# Sparkfun_TMP117_Qwiic.net
KiCad netlist of a schematic drawn in EAGLE
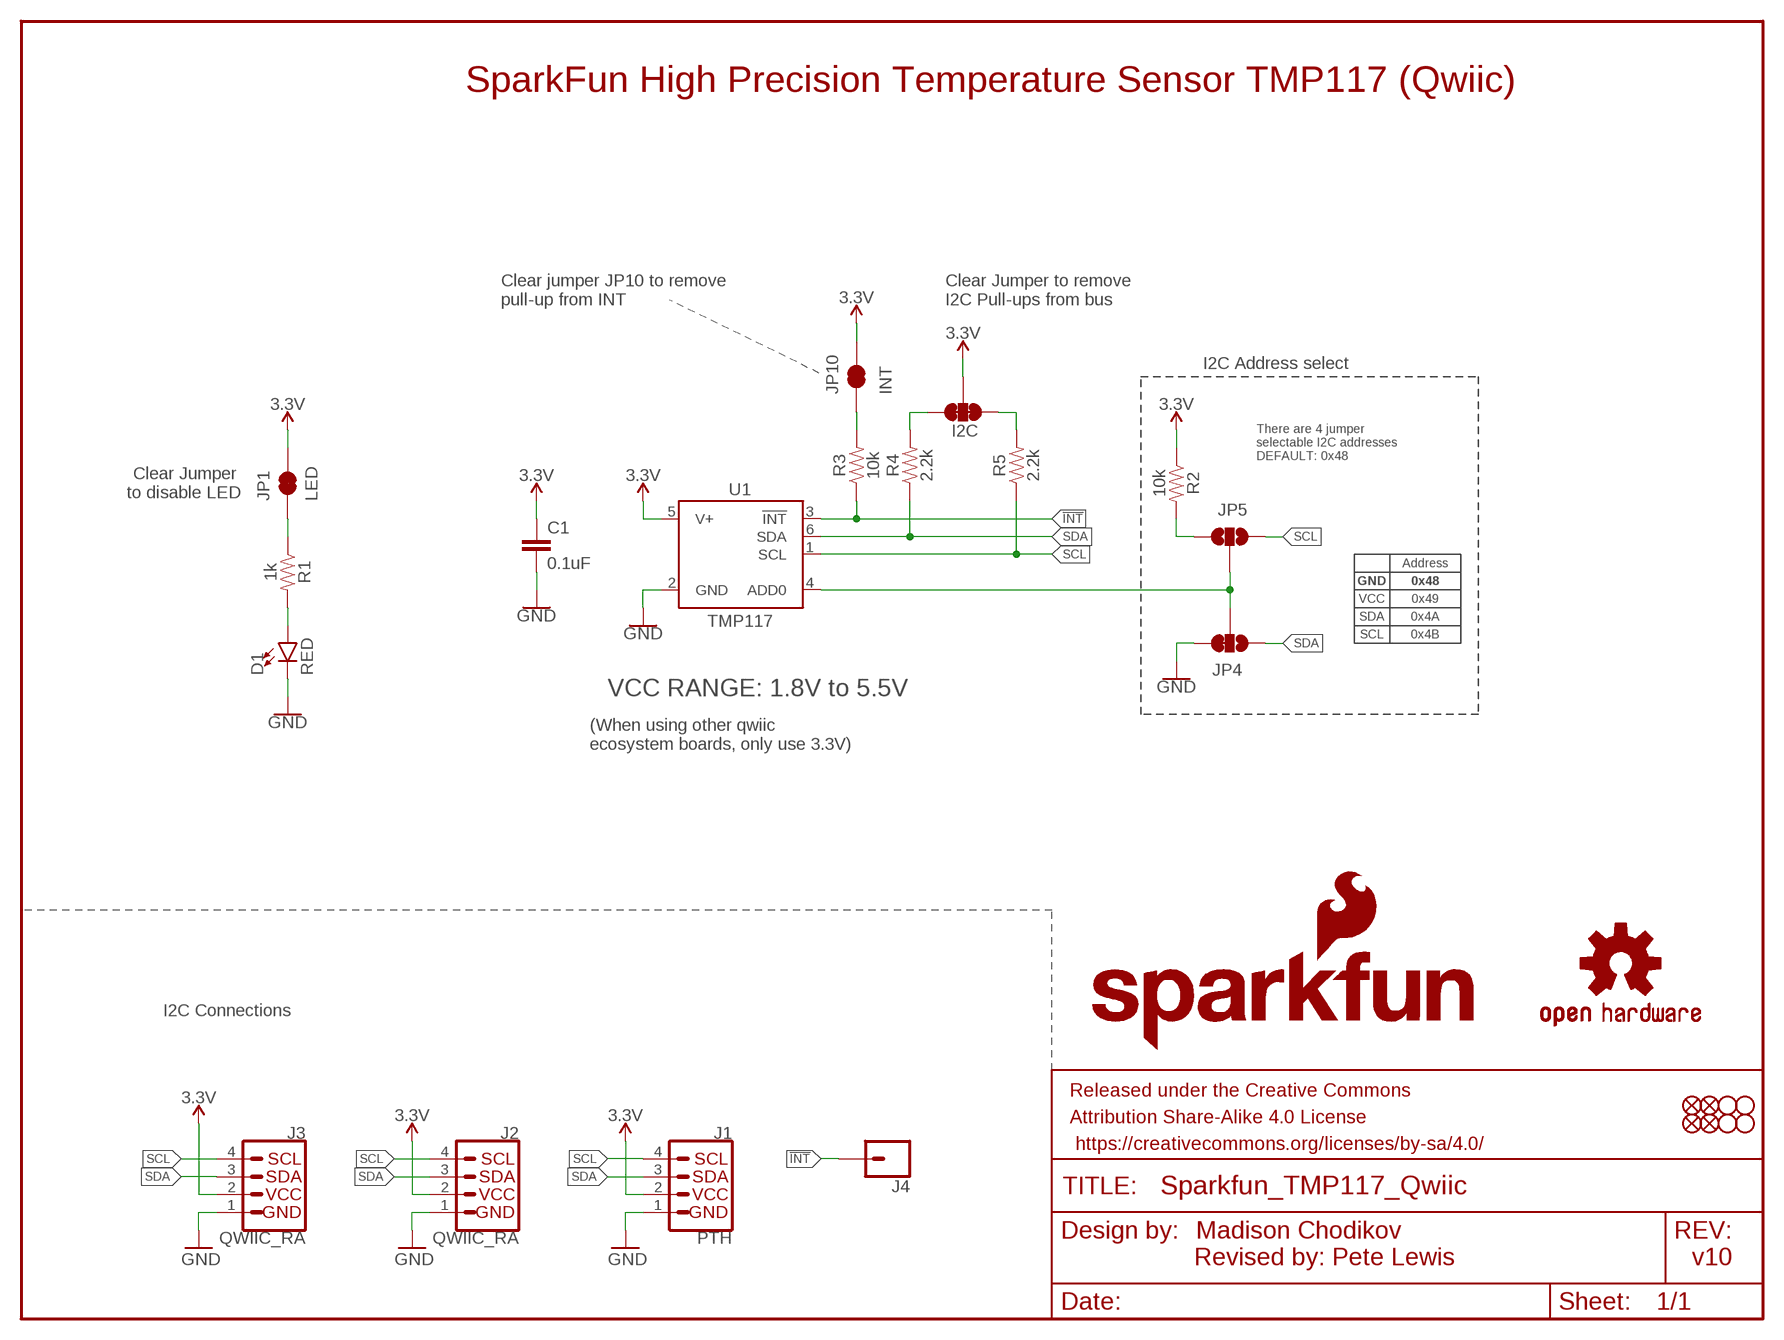
[diagram p0: schematic, sheet 1]

(export (version "E")
  (design (tool "Eeschema 10.0.6"))
  (components
    (comp (ref "C1")
      (value "0.1uF")
      (footprint "eagle-import:0603")
      (libsource (lib "eagle-import") (part "0.1UF-0603-25V-(+80/-20%)"))
    )
    (comp (ref "D1")
      (value "RED")
      (footprint "eagle-import:LED-0603")
      (libsource (lib "eagle-import") (part "LED-RED0603"))
    )
    (comp (ref "FD1")
      (value "FIDUCIALUFIDUCIAL")
      (footprint "eagle-import:FIDUCIAL-MICRO")
      (libsource (lib "eagle-import") (part "FIDUCIALUFIDUCIAL"))
    )
    (comp (ref "FD2")
      (value "FIDUCIALUFIDUCIAL")
      (footprint "eagle-import:FIDUCIAL-MICRO")
      (libsource (lib "eagle-import") (part "FIDUCIALUFIDUCIAL"))
    )
    (comp (ref "FD3")
      (value "FIDUCIALUFIDUCIAL")
      (footprint "eagle-import:FIDUCIAL-MICRO")
      (libsource (lib "eagle-import") (part "FIDUCIALUFIDUCIAL"))
    )
    (comp (ref "FD4")
      (value "FIDUCIALUFIDUCIAL")
      (footprint "eagle-import:FIDUCIAL-MICRO")
      (libsource (lib "eagle-import") (part "FIDUCIALUFIDUCIAL"))
    )
    (comp (ref "FRAME1")
      (value "FRAME-LETTER")
      (footprint "eagle-import:CREATIVE_COMMONS")
      (libsource (lib "eagle-import") (part "FRAME-LETTER"))
    )
    (comp (ref "I2C")
      (value "JUMPER-SMT_3_2-NC_TRACE_SILK")
      (footprint "eagle-import:SMT-JUMPER_3_2-NC_TRACE_SILK")
      (libsource (lib "eagle-import") (part "JUMPER-SMT_3_2-NC_TRACE_SILK"))
    )
    (comp (ref "J1")
      (value "PTH")
      (footprint "eagle-import:1X04_NO_SILK")
      (libsource (lib "eagle-import") (part "I2C_STANDARD_NO_SILK"))
    )
    (comp (ref "J2")
      (value "QWIIC_RA")
      (footprint "eagle-import:JST04_1MM_RA")
      (libsource (lib "eagle-import") (part "QWIIC_CONNECTORJS-1MM"))
    )
    (comp (ref "J3")
      (value "QWIIC_RA")
      (footprint "eagle-import:JST04_1MM_RA")
      (libsource (lib "eagle-import") (part "QWIIC_CONNECTORJS-1MM"))
    )
    (comp (ref "J4")
      (value "CONN_01PTH_NO_SILK_YES_STOP")
      (footprint "eagle-import:1X01_NO_SILK")
      (libsource (lib "eagle-import") (part "CONN_01PTH_NO_SILK_YES_STOP"))
    )
    (comp (ref "JP1")
      (value "LED")
      (footprint "eagle-import:SMT-JUMPER_2_NC_TRACE_SILK")
      (libsource (lib "eagle-import") (part "JUMPER-SMT_2_NC_TRACE_SILK"))
    )
    (comp (ref "JP2")
      (value "STAND-OFF")
      (footprint "eagle-import:STAND-OFF")
      (libsource (lib "eagle-import") (part "STAND-OFF"))
    )
    (comp (ref "JP3")
      (value "STAND-OFF")
      (footprint "eagle-import:STAND-OFF")
      (libsource (lib "eagle-import") (part "STAND-OFF"))
    )
    (comp (ref "JP4")
      (value "JUMPER-SMT_3_1-NC_TRACE_NO-SILK")
      (footprint "eagle-import:SMT-JUMPER_3_1-NC_TRACE_NO-SILK")
      (libsource (lib "eagle-import") (part "JUMPER-SMT_3_1-NC_TRACE_NO-SILK"))
    )
    (comp (ref "JP5")
      (value "JUMPER-SMT_3_NO_NO_SILK")
      (footprint "eagle-import:SMT-JUMPER_3_0-NO_TRACE_NO-SILK")
      (libsource (lib "eagle-import") (part "JUMPER-SMT_3_NO_NO_SILK"))
    )
    (comp (ref "JP8")
      (value "STAND-OFF")
      (footprint "eagle-import:STAND-OFF")
      (libsource (lib "eagle-import") (part "STAND-OFF"))
    )
    (comp (ref "JP9")
      (value "STAND-OFF")
      (footprint "eagle-import:STAND-OFF")
      (libsource (lib "eagle-import") (part "STAND-OFF"))
    )
    (comp (ref "JP10")
      (value "INT")
      (footprint "eagle-import:SMT-JUMPER_2_NC_TRACE_SILK")
      (libsource (lib "eagle-import") (part "JUMPER-SMT_2_NC_TRACE_SILK"))
    )
    (comp (ref "LOGO1")
      (value "OSHW-LOGOMINI")
      (footprint "eagle-import:OSHW-LOGO-MINI")
      (libsource (lib "eagle-import") (part "OSHW-LOGOMINI"))
    )
    (comp (ref "LOGO4")
      (value "SFE_LOGO_NAME_FLAME.1_INCH")
      (footprint "eagle-import:SFE_LOGO_NAME_FLAME_.1")
      (libsource (lib "eagle-import") (part "SFE_LOGO_NAME_FLAME.1_INCH"))
    )
    (comp (ref "R1")
      (value "1k")
      (footprint "eagle-import:0603")
      (libsource (lib "eagle-import") (part "1KOHM-0603-1/10W-1%"))
    )
    (comp (ref "R2")
      (value "10k")
      (footprint "eagle-import:0603")
      (libsource (lib "eagle-import") (part "10KOHM-0603-1/10W-1%"))
    )
    (comp (ref "R3")
      (value "10k")
      (footprint "eagle-import:0603")
      (libsource (lib "eagle-import") (part "10KOHM-0603-1/10W-1%"))
    )
    (comp (ref "R4")
      (value "2.2k")
      (footprint "eagle-import:0603")
      (libsource (lib "eagle-import") (part "2.2KOHM-0603-1/10W-1%"))
    )
    (comp (ref "R5")
      (value "2.2k")
      (footprint "eagle-import:0603")
      (libsource (lib "eagle-import") (part "2.2KOHM-0603-1/10W-1%"))
    )
    (comp (ref "U1")
      (value "TMP117")
      (footprint "eagle-import:TMP117")
      (libsource (lib "eagle-import") (part "TMP117"))
    )
  )
  (nets
    (net (code "1") (name "/~{INT}") (class "Default")
      (node (ref "J4") (pin "1") (pinfunction "1_1") (pintype "passive"))
      (node (ref "R3") (pin "1") (pinfunction "1_1") (pintype "passive"))
      (node (ref "U1") (pin "3") (pinfunction "~{INT}_3") (pintype "bidirectional"))
    )
    (net (code "2") (name "3.3V") (class "Default")
      (node (ref "C1") (pin "1") (pinfunction "1_1") (pintype "passive"))
      (node (ref "I2C") (pin "2") (pinfunction "2_2") (pintype "passive"))
      (node (ref "J1") (pin "2") (pinfunction "2_2") (pintype "power_in"))
      (node (ref "J2") (pin "2") (pinfunction "2_2") (pintype "power_in"))
      (node (ref "J3") (pin "2") (pinfunction "2_2") (pintype "power_in"))
      (node (ref "JP1") (pin "2") (pinfunction "2_2") (pintype "passive"))
      (node (ref "JP10") (pin "2") (pinfunction "2_2") (pintype "passive"))
      (node (ref "R2") (pin "1") (pinfunction "1_1") (pintype "passive"))
      (node (ref "U1") (pin "5") (pinfunction "V+_5") (pintype "power_in"))
    )
    (net (code "3") (name "GND") (class "Default")
      (node (ref "C1") (pin "2") (pinfunction "2_2") (pintype "passive"))
      (node (ref "D1") (pin "C") (pinfunction "C_C") (pintype "passive"))
      (node (ref "J1") (pin "1") (pinfunction "1_1") (pintype "power_in"))
      (node (ref "J2") (pin "1") (pinfunction "1_1") (pintype "power_in"))
      (node (ref "J3") (pin "1") (pinfunction "1_1") (pintype "power_in"))
      (node (ref "JP4") (pin "3") (pinfunction "3_3") (pintype "passive"))
      (node (ref "U1") (pin "2") (pinfunction "GND_2") (pintype "bidirectional"))
    )
    (net (code "4") (name "Net-(D1-PadA)") (class "Default")
      (node (ref "D1") (pin "A") (pinfunction "A_A") (pintype "passive"))
      (node (ref "R1") (pin "2") (pinfunction "2_2") (pintype "passive"))
    )
    (net (code "5") (name "Net-(I2C-Pad1)") (class "Default")
      (node (ref "I2C") (pin "1") (pinfunction "1_1") (pintype "passive"))
      (node (ref "R5") (pin "2") (pinfunction "2_2") (pintype "passive"))
    )
    (net (code "6") (name "Net-(I2C-Pad3)") (class "Default")
      (node (ref "I2C") (pin "3") (pinfunction "3_3") (pintype "passive"))
      (node (ref "R4") (pin "2") (pinfunction "2_2") (pintype "passive"))
    )
    (net (code "7") (name "Net-(JP1-Pad1)") (class "Default")
      (node (ref "JP1") (pin "1") (pinfunction "1_1") (pintype "passive"))
      (node (ref "R1") (pin "1") (pinfunction "1_1") (pintype "passive"))
    )
    (net (code "8") (name "Net-(JP5-Pad1)") (class "Default")
      (node (ref "JP5") (pin "1") (pinfunction "1_1") (pintype "passive"))
      (node (ref "R2") (pin "2") (pinfunction "2_2") (pintype "passive"))
    )
    (net (code "9") (name "Net-(JP10-Pad1)") (class "Default")
      (node (ref "JP10") (pin "1") (pinfunction "1_1") (pintype "passive"))
      (node (ref "R3") (pin "2") (pinfunction "2_2") (pintype "passive"))
    )
    (net (code "10") (name "Net-(U1-ADD0)") (class "Default")
      (node (ref "JP4") (pin "2") (pinfunction "2_2") (pintype "passive"))
      (node (ref "JP5") (pin "2") (pinfunction "2_2") (pintype "passive"))
      (node (ref "U1") (pin "4") (pinfunction "ADD0_4") (pintype "bidirectional"))
    )
    (net (code "11") (name "SCL") (class "Default")
      (node (ref "J1") (pin "4") (pinfunction "4_4") (pintype "passive"))
      (node (ref "J2") (pin "4") (pinfunction "4_4") (pintype "passive"))
      (node (ref "J3") (pin "4") (pinfunction "4_4") (pintype "passive"))
      (node (ref "JP5") (pin "3") (pinfunction "3_3") (pintype "passive"))
      (node (ref "R5") (pin "1") (pinfunction "1_1") (pintype "passive"))
      (node (ref "U1") (pin "1") (pinfunction "SCL_1") (pintype "bidirectional"))
    )
    (net (code "12") (name "SDA") (class "Default")
      (node (ref "J1") (pin "3") (pinfunction "3_3") (pintype "passive"))
      (node (ref "J2") (pin "3") (pinfunction "3_3") (pintype "passive"))
      (node (ref "J3") (pin "3") (pinfunction "3_3") (pintype "passive"))
      (node (ref "JP4") (pin "1") (pinfunction "1_1") (pintype "passive"))
      (node (ref "R4") (pin "1") (pinfunction "1_1") (pintype "passive"))
      (node (ref "U1") (pin "6") (pinfunction "SDA_6") (pintype "bidirectional"))
    )
  )
)
